# voice_board_kombi_w_gp_ordered-210217.net
KiCad netlist of a schematic drawn in EAGLE
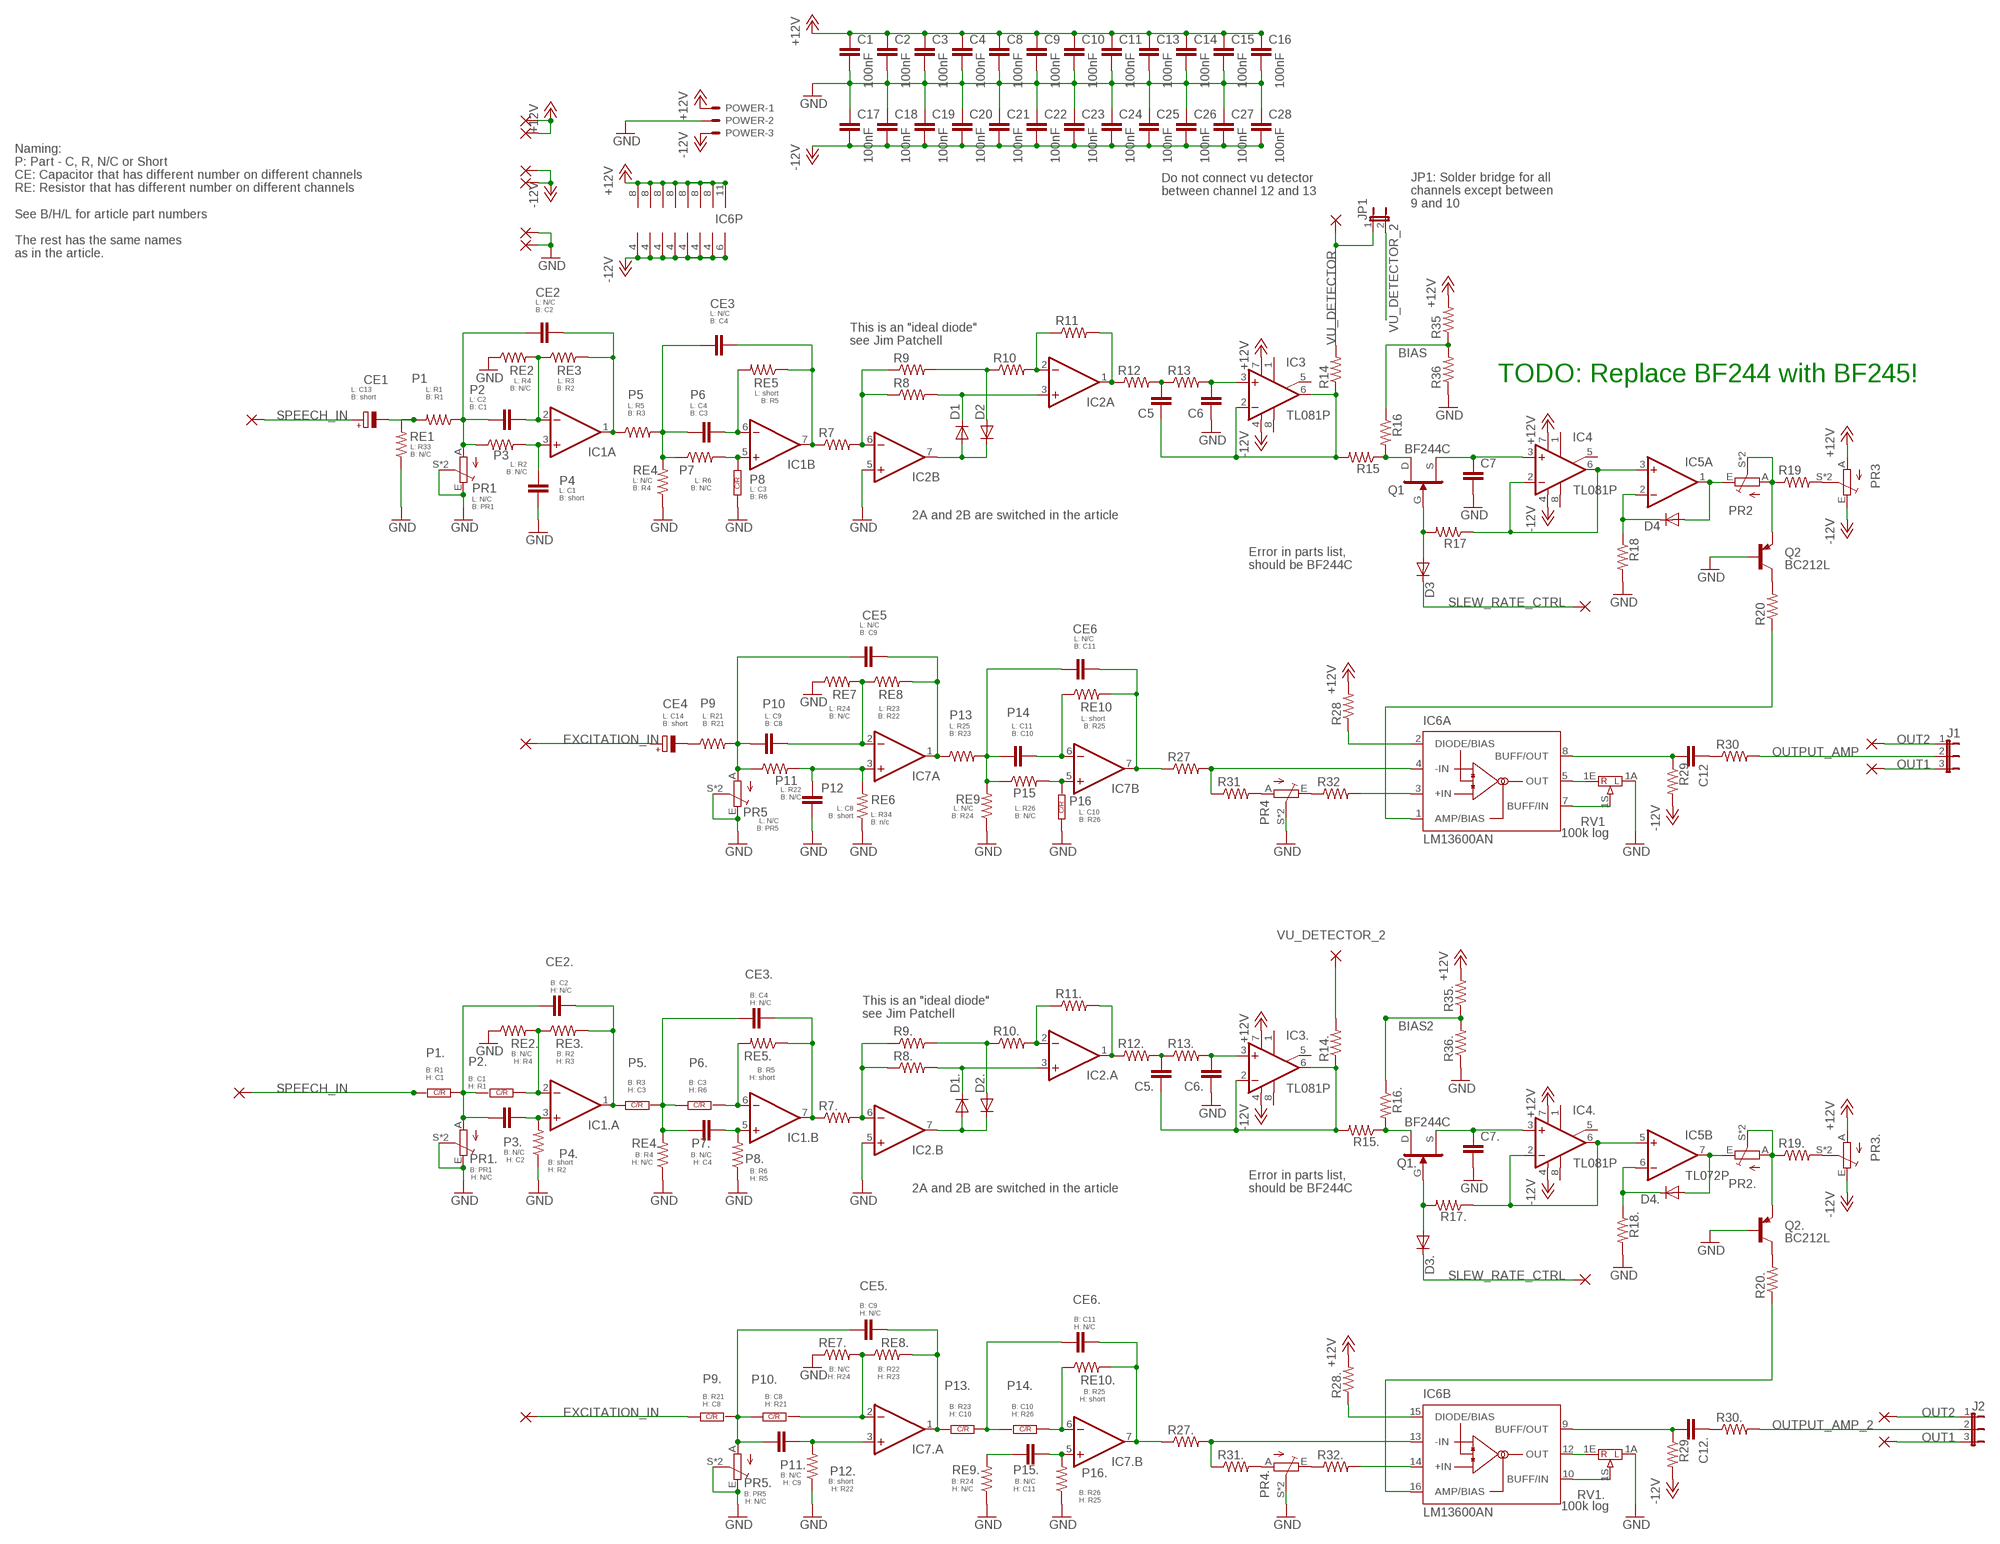
[diagram p0: schematic, sheet 1]

(export (version "E")
  (design (tool "Eeschema 10.0.6"))
  (components
    (comp (ref "C1")
      (value "100nF")
      (footprint "eagle-import:C0603")
      (libsource (lib "eagle-import") (part "C-EUC0603"))
    )
    (comp (ref "C2")
      (value "100nF")
      (footprint "eagle-import:C0603")
      (libsource (lib "eagle-import") (part "C-EUC0603"))
    )
    (comp (ref "C3")
      (value "100nF")
      (footprint "eagle-import:C0603")
      (libsource (lib "eagle-import") (part "C-EUC0603"))
    )
    (comp (ref "C4")
      (value "100nF")
      (footprint "eagle-import:C0603")
      (libsource (lib "eagle-import") (part "C-EUC0603"))
    )
    (comp (ref "C5")
      (value "C-EU050-035X075")
      (footprint "eagle-import:C050-035X075")
      (libsource (lib "eagle-import") (part "C-EU050-035X075"))
    )
    (comp (ref "C5.")
      (value "C-EU050-035X075")
      (footprint "eagle-import:C050-035X075")
      (libsource (lib "eagle-import") (part "C-EU050-035X075"))
    )
    (comp (ref "C6")
      (value "C-EU050-035X075")
      (footprint "eagle-import:C050-035X075")
      (libsource (lib "eagle-import") (part "C-EU050-035X075"))
    )
    (comp (ref "C6.")
      (value "C-EU050-035X075")
      (footprint "eagle-import:C050-035X075")
      (libsource (lib "eagle-import") (part "C-EU050-035X075"))
    )
    (comp (ref "C7")
      (value "C-EU050-035X075")
      (footprint "eagle-import:C050-035X075")
      (libsource (lib "eagle-import") (part "C-EU050-035X075"))
    )
    (comp (ref "C7.")
      (value "C-EU050-035X075")
      (footprint "eagle-import:C050-035X075")
      (libsource (lib "eagle-import") (part "C-EU050-035X075"))
    )
    (comp (ref "C8")
      (value "100nF")
      (footprint "eagle-import:C0603")
      (libsource (lib "eagle-import") (part "C-EUC0603"))
    )
    (comp (ref "C9")
      (value "100nF")
      (footprint "eagle-import:C0603")
      (libsource (lib "eagle-import") (part "C-EUC0603"))
    )
    (comp (ref "C10")
      (value "100nF")
      (footprint "eagle-import:C0603")
      (libsource (lib "eagle-import") (part "C-EUC0603"))
    )
    (comp (ref "C11")
      (value "100nF")
      (footprint "eagle-import:C0603")
      (libsource (lib "eagle-import") (part "C-EUC0603"))
    )
    (comp (ref "C12")
      (value "C-EU050-035X075")
      (footprint "eagle-import:C050-035X075")
      (libsource (lib "eagle-import") (part "C-EU050-035X075"))
    )
    (comp (ref "C12.")
      (value "C-EU050-035X075")
      (footprint "eagle-import:C050-035X075")
      (libsource (lib "eagle-import") (part "C-EU050-035X075"))
    )
    (comp (ref "C13")
      (value "100nF")
      (footprint "eagle-import:C0603")
      (libsource (lib "eagle-import") (part "C-EUC0603"))
    )
    (comp (ref "C14")
      (value "100nF")
      (footprint "eagle-import:C0603")
      (libsource (lib "eagle-import") (part "C-EUC0603"))
    )
    (comp (ref "C15")
      (value "100nF")
      (footprint "eagle-import:C0603")
      (libsource (lib "eagle-import") (part "C-EUC0603"))
    )
    (comp (ref "C16")
      (value "100nF")
      (footprint "eagle-import:C0603")
      (libsource (lib "eagle-import") (part "C-EUC0603"))
    )
    (comp (ref "C17")
      (value "100nF")
      (footprint "eagle-import:C0603")
      (libsource (lib "eagle-import") (part "C-EUC0603"))
    )
    (comp (ref "C18")
      (value "100nF")
      (footprint "eagle-import:C0603")
      (libsource (lib "eagle-import") (part "C-EUC0603"))
    )
    (comp (ref "C19")
      (value "100nF")
      (footprint "eagle-import:C0603")
      (libsource (lib "eagle-import") (part "C-EUC0603"))
    )
    (comp (ref "C20")
      (value "100nF")
      (footprint "eagle-import:C0603")
      (libsource (lib "eagle-import") (part "C-EUC0603"))
    )
    (comp (ref "C21")
      (value "100nF")
      (footprint "eagle-import:C0603")
      (libsource (lib "eagle-import") (part "C-EUC0603"))
    )
    (comp (ref "C22")
      (value "100nF")
      (footprint "eagle-import:C0603")
      (libsource (lib "eagle-import") (part "C-EUC0603"))
    )
    (comp (ref "C23")
      (value "100nF")
      (footprint "eagle-import:C0603")
      (libsource (lib "eagle-import") (part "C-EUC0603"))
    )
    (comp (ref "C24")
      (value "100nF")
      (footprint "eagle-import:C0603")
      (libsource (lib "eagle-import") (part "C-EUC0603"))
    )
    (comp (ref "C25")
      (value "100nF")
      (footprint "eagle-import:C0603")
      (libsource (lib "eagle-import") (part "C-EUC0603"))
    )
    (comp (ref "C26")
      (value "100nF")
      (footprint "eagle-import:C0603")
      (libsource (lib "eagle-import") (part "C-EUC0603"))
    )
    (comp (ref "C27")
      (value "100nF")
      (footprint "eagle-import:C0603")
      (libsource (lib "eagle-import") (part "C-EUC0603"))
    )
    (comp (ref "C28")
      (value "100nF")
      (footprint "eagle-import:C0603")
      (libsource (lib "eagle-import") (part "C-EUC0603"))
    )
    (comp (ref "CE1")
      (value "CPOL-EUE2-4")
      (footprint "eagle-import:E2-4")
      (libsource (lib "eagle-import") (part "CPOL-EUE2-4"))
    )
    (comp (ref "CE2")
      (value "C-EU050-035X075")
      (footprint "eagle-import:C050-035X075")
      (libsource (lib "eagle-import") (part "C-EU050-035X075"))
    )
    (comp (ref "CE2.")
      (value "C-EU050-035X075")
      (footprint "eagle-import:C050-035X075")
      (libsource (lib "eagle-import") (part "C-EU050-035X075"))
    )
    (comp (ref "CE3")
      (value "C-EU050-035X075")
      (footprint "eagle-import:C050-035X075")
      (libsource (lib "eagle-import") (part "C-EU050-035X075"))
    )
    (comp (ref "CE3.")
      (value "C-EU050-035X075")
      (footprint "eagle-import:C050-035X075")
      (libsource (lib "eagle-import") (part "C-EU050-035X075"))
    )
    (comp (ref "CE4")
      (value "CPOL-EUE2-4")
      (footprint "eagle-import:E2-4")
      (libsource (lib "eagle-import") (part "CPOL-EUE2-4"))
    )
    (comp (ref "CE5")
      (value "C-EU050-035X075")
      (footprint "eagle-import:C050-035X075")
      (libsource (lib "eagle-import") (part "C-EU050-035X075"))
    )
    (comp (ref "CE5.")
      (value "C-EU050-035X075")
      (footprint "eagle-import:C050-035X075")
      (libsource (lib "eagle-import") (part "C-EU050-035X075"))
    )
    (comp (ref "CE6")
      (value "C-EU050-035X075")
      (footprint "eagle-import:C050-035X075")
      (libsource (lib "eagle-import") (part "C-EU050-035X075"))
    )
    (comp (ref "CE6.")
      (value "C-EU050-035X075")
      (footprint "eagle-import:C050-035X075")
      (libsource (lib "eagle-import") (part "C-EU050-035X075"))
    )
    (comp (ref "D1")
      (value "DIODE-D-5")
      (footprint "eagle-import:D-5")
      (libsource (lib "eagle-import") (part "DIODE-D-5"))
    )
    (comp (ref "D1.")
      (value "DIODE-D-5")
      (footprint "eagle-import:D-5")
      (libsource (lib "eagle-import") (part "DIODE-D-5"))
    )
    (comp (ref "D2")
      (value "DIODE-D-5")
      (footprint "eagle-import:D-5")
      (libsource (lib "eagle-import") (part "DIODE-D-5"))
    )
    (comp (ref "D2.")
      (value "DIODE-D-5")
      (footprint "eagle-import:D-5")
      (libsource (lib "eagle-import") (part "DIODE-D-5"))
    )
    (comp (ref "D3")
      (value "DIODE-D-5")
      (footprint "eagle-import:D-5")
      (libsource (lib "eagle-import") (part "DIODE-D-5"))
    )
    (comp (ref "D3.")
      (value "DIODE-D-5")
      (footprint "eagle-import:D-5")
      (libsource (lib "eagle-import") (part "DIODE-D-5"))
    )
    (comp (ref "D4")
      (value "DIODE-D-5")
      (footprint "eagle-import:D-5")
      (libsource (lib "eagle-import") (part "DIODE-D-5"))
    )
    (comp (ref "D4.")
      (value "DIODE-D-5")
      (footprint "eagle-import:D-5")
      (libsource (lib "eagle-import") (part "DIODE-D-5"))
    )
    (comp (ref "IC1")
      (value "TL072P")
      (footprint "eagle-import:DIL08")
      (libsource (lib "eagle-import") (part "TL072P"))
    )
    (comp (ref "IC1.")
      (value "TL072P")
      (footprint "eagle-import:DIL08")
      (libsource (lib "eagle-import") (part "TL072P"))
    )
    (comp (ref "IC2")
      (value "TL072P")
      (footprint "eagle-import:DIL08")
      (libsource (lib "eagle-import") (part "TL072P"))
    )
    (comp (ref "IC2.")
      (value "TL072P")
      (footprint "eagle-import:DIL08")
      (libsource (lib "eagle-import") (part "TL072P"))
    )
    (comp (ref "IC3")
      (value "TL081P")
      (footprint "eagle-import:DIL08")
      (libsource (lib "eagle-import") (part "TL081P"))
    )
    (comp (ref "IC3.")
      (value "TL081P")
      (footprint "eagle-import:DIL08")
      (libsource (lib "eagle-import") (part "TL081P"))
    )
    (comp (ref "IC4")
      (value "TL081P")
      (footprint "eagle-import:DIL08")
      (libsource (lib "eagle-import") (part "TL081P"))
    )
    (comp (ref "IC4.")
      (value "TL081P")
      (footprint "eagle-import:DIL08")
      (libsource (lib "eagle-import") (part "TL081P"))
    )
    (comp (ref "IC5")
      (value "TL072P")
      (footprint "eagle-import:DIL08")
      (libsource (lib "eagle-import") (part "TL072P"))
    )
    (comp (ref "IC6")
      (value "LM13600AN")
      (footprint "eagle-import:DIL16")
      (libsource (lib "eagle-import") (part "LM13600NA"))
    )
    (comp (ref "IC7")
      (value "TL072P")
      (footprint "eagle-import:DIL08")
      (libsource (lib "eagle-import") (part "TL072P"))
    )
    (comp (ref "IC7.")
      (value "TL072P")
      (footprint "eagle-import:DIL08")
      (libsource (lib "eagle-import") (part "TL072P"))
    )
    (comp (ref "J1")
      (value "JP2E")
      (footprint "eagle-import:JP2")
      (libsource (lib "eagle-import") (part "JP2E"))
    )
    (comp (ref "J2")
      (value "JP2E")
      (footprint "eagle-import:JP2")
      (libsource (lib "eagle-import") (part "JP2E"))
    )
    (comp (ref "JP1")
      (value "JP1E")
      (footprint "eagle-import:JP1")
      (libsource (lib "eagle-import") (part "JP1E"))
    )
    (comp (ref "P1")
      (value "R-US_0207/7")
      (footprint "eagle-import:0207_7")
      (libsource (lib "eagle-import") (part "R-US_0207/7"))
    )
    (comp (ref "P1.")
      (value "C-OR-R050_075-035X100")
      (footprint "eagle-import:P050_075-035X100J")
      (libsource (lib "eagle-import") (part "C-OR-R050_075-035X100"))
    )
    (comp (ref "P2")
      (value "C-EU050-035X075")
      (footprint "eagle-import:C050-035X075")
      (libsource (lib "eagle-import") (part "C-EU050-035X075"))
    )
    (comp (ref "P2.")
      (value "C-OR-R050_075-035X100")
      (footprint "eagle-import:P050_075-035X100J")
      (libsource (lib "eagle-import") (part "C-OR-R050_075-035X100"))
    )
    (comp (ref "P3")
      (value "R-US_0207/7")
      (footprint "eagle-import:0207_7")
      (libsource (lib "eagle-import") (part "R-US_0207/7"))
    )
    (comp (ref "P3.")
      (value "C-EU050-035X075")
      (footprint "eagle-import:C050-035X075")
      (libsource (lib "eagle-import") (part "C-EU050-035X075"))
    )
    (comp (ref "P4")
      (value "C-EU050-035X075")
      (footprint "eagle-import:C050-035X075")
      (libsource (lib "eagle-import") (part "C-EU050-035X075"))
    )
    (comp (ref "P4.")
      (value "R-US_0207/7")
      (footprint "eagle-import:0207_7")
      (libsource (lib "eagle-import") (part "R-US_0207/7"))
    )
    (comp (ref "P5")
      (value "R-US_0207/7")
      (footprint "eagle-import:0207_7")
      (libsource (lib "eagle-import") (part "R-US_0207/7"))
    )
    (comp (ref "P5.")
      (value "C-OR-R050_075-035X100")
      (footprint "eagle-import:P050_075-035X100J")
      (libsource (lib "eagle-import") (part "C-OR-R050_075-035X100"))
    )
    (comp (ref "P6")
      (value "C-EU050-035X075")
      (footprint "eagle-import:C050-035X075")
      (libsource (lib "eagle-import") (part "C-EU050-035X075"))
    )
    (comp (ref "P6.")
      (value "C-OR-R050_075-035X100")
      (footprint "eagle-import:P050_075-035X100J")
      (libsource (lib "eagle-import") (part "C-OR-R050_075-035X100"))
    )
    (comp (ref "P7")
      (value "R-US_0207/7")
      (footprint "eagle-import:0207_7")
      (libsource (lib "eagle-import") (part "R-US_0207/7"))
    )
    (comp (ref "P7.")
      (value "C-EU050-035X075")
      (footprint "eagle-import:C050-035X075")
      (libsource (lib "eagle-import") (part "C-EU050-035X075"))
    )
    (comp (ref "P8")
      (value "C-OR-R050_075-035X100")
      (footprint "eagle-import:P050_075-035X100J")
      (libsource (lib "eagle-import") (part "C-OR-R050_075-035X100"))
    )
    (comp (ref "P8.")
      (value "R-US_0207/7")
      (footprint "eagle-import:0207_7")
      (libsource (lib "eagle-import") (part "R-US_0207/7"))
    )
    (comp (ref "P9")
      (value "R-US_0207/7")
      (footprint "eagle-import:0207_7")
      (libsource (lib "eagle-import") (part "R-US_0207/7"))
    )
    (comp (ref "P9.")
      (value "C-OR-R050_075-035X100")
      (footprint "eagle-import:P050_075-035X100J")
      (libsource (lib "eagle-import") (part "C-OR-R050_075-035X100"))
    )
    (comp (ref "P10")
      (value "C-EU050-035X075")
      (footprint "eagle-import:C050-035X075")
      (libsource (lib "eagle-import") (part "C-EU050-035X075"))
    )
    (comp (ref "P10.")
      (value "C-OR-R050_075-035X100")
      (footprint "eagle-import:P050_075-035X100J")
      (libsource (lib "eagle-import") (part "C-OR-R050_075-035X100"))
    )
    (comp (ref "P11")
      (value "R-US_0207/7")
      (footprint "eagle-import:0207_7")
      (libsource (lib "eagle-import") (part "R-US_0207/7"))
    )
    (comp (ref "P11.")
      (value "C-EU050-035X075")
      (footprint "eagle-import:C050-035X075")
      (libsource (lib "eagle-import") (part "C-EU050-035X075"))
    )
    (comp (ref "P12")
      (value "C-EU050-035X075")
      (footprint "eagle-import:C050-035X075")
      (libsource (lib "eagle-import") (part "C-EU050-035X075"))
    )
    (comp (ref "P12.")
      (value "R-US_0207/7")
      (footprint "eagle-import:0207_7")
      (libsource (lib "eagle-import") (part "R-US_0207/7"))
    )
    (comp (ref "P13")
      (value "R-US_0207/7")
      (footprint "eagle-import:0207_7")
      (libsource (lib "eagle-import") (part "R-US_0207/7"))
    )
    (comp (ref "P13.")
      (value "C-OR-R050_075-035X100")
      (footprint "eagle-import:P050_075-035X100J")
      (libsource (lib "eagle-import") (part "C-OR-R050_075-035X100"))
    )
    (comp (ref "P14")
      (value "C-EU050-035X075")
      (footprint "eagle-import:C050-035X075")
      (libsource (lib "eagle-import") (part "C-EU050-035X075"))
    )
    (comp (ref "P14.")
      (value "C-OR-R050_075-035X100")
      (footprint "eagle-import:P050_075-035X100J")
      (libsource (lib "eagle-import") (part "C-OR-R050_075-035X100"))
    )
    (comp (ref "P15")
      (value "R-US_0207/7")
      (footprint "eagle-import:0207_7")
      (libsource (lib "eagle-import") (part "R-US_0207/7"))
    )
    (comp (ref "P15.")
      (value "C-EU050-035X075")
      (footprint "eagle-import:C050-035X075")
      (libsource (lib "eagle-import") (part "C-EU050-035X075"))
    )
    (comp (ref "P16")
      (value "C-OR-R050_075-035X100")
      (footprint "eagle-import:P050_075-035X100J")
      (libsource (lib "eagle-import") (part "C-OR-R050_075-035X100"))
    )
    (comp (ref "P16.")
      (value "R-US_0207/7")
      (footprint "eagle-import:0207_7")
      (libsource (lib "eagle-import") (part "R-US_0207/7"))
    )
    (comp (ref "PAD1")
      (value "WIREPAD2,54/1,1")
      (footprint "eagle-import:2,54_1,1")
      (libsource (lib "eagle-import") (part "WIREPAD2,54/1,1"))
    )
    (comp (ref "PAD2")
      (value "WIREPAD2,54/1,1")
      (footprint "eagle-import:2,54_1,1")
      (libsource (lib "eagle-import") (part "WIREPAD2,54/1,1"))
    )
    (comp (ref "PAD3")
      (value "WIREPAD2,54/1,1")
      (footprint "eagle-import:2,54_1,1")
      (libsource (lib "eagle-import") (part "WIREPAD2,54/1,1"))
    )
    (comp (ref "PAD4")
      (value "WIREPAD2,54/1,1")
      (footprint "eagle-import:2,54_1,1")
      (libsource (lib "eagle-import") (part "WIREPAD2,54/1,1"))
    )
    (comp (ref "PAD5")
      (value "WIREPAD2,54/1,1")
      (footprint "eagle-import:2,54_1,1")
      (libsource (lib "eagle-import") (part "WIREPAD2,54/1,1"))
    )
    (comp (ref "PAD6")
      (value "WIREPAD2,54/1,1")
      (footprint "eagle-import:2,54_1,1")
      (libsource (lib "eagle-import") (part "WIREPAD2,54/1,1"))
    )
    (comp (ref "PAD7")
      (value "WIREPAD2,54/1,1")
      (footprint "eagle-import:2,54_1,1")
      (libsource (lib "eagle-import") (part "WIREPAD2,54/1,1"))
    )
    (comp (ref "PAD8")
      (value "WIREPAD2,54/1,1")
      (footprint "eagle-import:2,54_1,1")
      (libsource (lib "eagle-import") (part "WIREPAD2,54/1,1"))
    )
    (comp (ref "PAD9")
      (value "WIREPAD2,54/1,1")
      (footprint "eagle-import:2,54_1,1")
      (libsource (lib "eagle-import") (part "WIREPAD2,54/1,1"))
    )
    (comp (ref "PAD10")
      (value "WIREPAD2,54/1,1")
      (footprint "eagle-import:2,54_1,1")
      (libsource (lib "eagle-import") (part "WIREPAD2,54/1,1"))
    )
    (comp (ref "PAD11")
      (value "WIREPAD2,54/1,1")
      (footprint "eagle-import:2,54_1,1")
      (libsource (lib "eagle-import") (part "WIREPAD2,54/1,1"))
    )
    (comp (ref "PAD12")
      (value "WIREPAD2,54/1,1")
      (footprint "eagle-import:2,54_1,1")
      (libsource (lib "eagle-import") (part "WIREPAD2,54/1,1"))
    )
    (comp (ref "PAD13")
      (value "WIREPAD2,54/1,1")
      (footprint "eagle-import:2,54_1,1")
      (libsource (lib "eagle-import") (part "WIREPAD2,54/1,1"))
    )
    (comp (ref "PAD14")
      (value "WIREPAD2,54/1,1")
      (footprint "eagle-import:2,54_1,1")
      (libsource (lib "eagle-import") (part "WIREPAD2,54/1,1"))
    )
    (comp (ref "PAD15")
      (value "WIREPAD2,54/1,1")
      (footprint "eagle-import:2,54_1,1")
      (libsource (lib "eagle-import") (part "WIREPAD2,54/1,1"))
    )
    (comp (ref "PAD16")
      (value "WIREPAD2,54/1,1")
      (footprint "eagle-import:2,54_1,1")
      (libsource (lib "eagle-import") (part "WIREPAD2,54/1,1"))
    )
    (comp (ref "PAD17")
      (value "WIREPAD2,54/1,1")
      (footprint "eagle-import:2,54_1,1")
      (libsource (lib "eagle-import") (part "WIREPAD2,54/1,1"))
    )
    (comp (ref "PAD18")
      (value "WIREPAD2,54/1,1")
      (footprint "eagle-import:2,54_1,1")
      (libsource (lib "eagle-import") (part "WIREPAD2,54/1,1"))
    )
    (comp (ref "POWER")
      (value "KK-156-3")
      (footprint "eagle-import:KK-156-3")
      (libsource (lib "eagle-import") (part "KK-156-3"))
    )
    (comp (ref "PR1")
      (value "TRIM_EU-PT10-R065")
      (footprint "eagle-import:MULTIPOT_2_J")
      (libsource (lib "eagle-import") (part "TRIM_EU-PT10-R065"))
    )
    (comp (ref "PR1.")
      (value "TRIM_EU-PT10-R065")
      (footprint "eagle-import:MULTIPOT_2_J")
      (libsource (lib "eagle-import") (part "TRIM_EU-PT10-R065"))
    )
    (comp (ref "PR2")
      (value "TRIM_EU-PT10-R065")
      (footprint "eagle-import:MULTIPOT_2_J")
      (libsource (lib "eagle-import") (part "TRIM_EU-PT10-R065"))
    )
    (comp (ref "PR2.")
      (value "TRIM_EU-PT10-R065")
      (footprint "eagle-import:MULTIPOT_2_J")
      (libsource (lib "eagle-import") (part "TRIM_EU-PT10-R065"))
    )
    (comp (ref "PR3")
      (value "TRIM_EU-PT10-R065")
      (footprint "eagle-import:MULTIPOT_2_J")
      (libsource (lib "eagle-import") (part "TRIM_EU-PT10-R065"))
    )
    (comp (ref "PR3.")
      (value "TRIM_EU-PT10-R065")
      (footprint "eagle-import:MULTIPOT_2_J")
      (libsource (lib "eagle-import") (part "TRIM_EU-PT10-R065"))
    )
    (comp (ref "PR4")
      (value "TRIM_EU-PT10-R065")
      (footprint "eagle-import:MULTIPOT_2_J")
      (libsource (lib "eagle-import") (part "TRIM_EU-PT10-R065"))
    )
    (comp (ref "PR4.")
      (value "TRIM_EU-PT10-R065")
      (footprint "eagle-import:MULTIPOT_2_J")
      (libsource (lib "eagle-import") (part "TRIM_EU-PT10-R065"))
    )
    (comp (ref "PR5")
      (value "TRIM_EU-PT10-R065")
      (footprint "eagle-import:MULTIPOT_2_J")
      (libsource (lib "eagle-import") (part "TRIM_EU-PT10-R065"))
    )
    (comp (ref "PR5.")
      (value "TRIM_EU-PT10-R065")
      (footprint "eagle-import:MULTIPOT_2_J")
      (libsource (lib "eagle-import") (part "TRIM_EU-PT10-R065"))
    )
    (comp (ref "Q1")
      (value "BF244C")
      (footprint "eagle-import:TO92-DGSD-J")
      (libsource (lib "eagle-import") (part "N-CHANNEL-JFET-JIL-DGSD"))
    )
    (comp (ref "Q1.")
      (value "BF244C")
      (footprint "eagle-import:TO92-DGSD-J")
      (libsource (lib "eagle-import") (part "N-CHANNEL-JFET-JIL-DGSD"))
    )
    (comp (ref "Q2")
      (value "BC212L")
      (footprint "eagle-import:TO92-ECB")
      (libsource (lib "eagle-import") (part "-PNP-TO92-ECB"))
    )
    (comp (ref "Q2.")
      (value "BC212L")
      (footprint "eagle-import:TO92-ECB")
      (libsource (lib "eagle-import") (part "-PNP-TO92-ECB"))
    )
    (comp (ref "R7")
      (value "R-US_0207/7")
      (footprint "eagle-import:0207_7")
      (libsource (lib "eagle-import") (part "R-US_0207/7"))
    )
    (comp (ref "R7.")
      (value "R-US_0207/7")
      (footprint "eagle-import:0207_7")
      (libsource (lib "eagle-import") (part "R-US_0207/7"))
    )
    (comp (ref "R8")
      (value "R-US_0207/7")
      (footprint "eagle-import:0207_7")
      (libsource (lib "eagle-import") (part "R-US_0207/7"))
    )
    (comp (ref "R8.")
      (value "R-US_0207/7")
      (footprint "eagle-import:0207_7")
      (libsource (lib "eagle-import") (part "R-US_0207/7"))
    )
    (comp (ref "R9")
      (value "R-US_0207/7")
      (footprint "eagle-import:0207_7")
      (libsource (lib "eagle-import") (part "R-US_0207/7"))
    )
    (comp (ref "R9.")
      (value "R-US_0207/7")
      (footprint "eagle-import:0207_7")
      (libsource (lib "eagle-import") (part "R-US_0207/7"))
    )
    (comp (ref "R10")
      (value "R-US_0207/7")
      (footprint "eagle-import:0207_7")
      (libsource (lib "eagle-import") (part "R-US_0207/7"))
    )
    (comp (ref "R10.")
      (value "R-US_0207/7")
      (footprint "eagle-import:0207_7")
      (libsource (lib "eagle-import") (part "R-US_0207/7"))
    )
    (comp (ref "R11")
      (value "R-US_0207/7")
      (footprint "eagle-import:0207_7")
      (libsource (lib "eagle-import") (part "R-US_0207/7"))
    )
    (comp (ref "R11.")
      (value "R-US_0207/7")
      (footprint "eagle-import:0207_7")
      (libsource (lib "eagle-import") (part "R-US_0207/7"))
    )
    (comp (ref "R12")
      (value "R-US_0207/7")
      (footprint "eagle-import:0207_7")
      (libsource (lib "eagle-import") (part "R-US_0207/7"))
    )
    (comp (ref "R12.")
      (value "R-US_0207/7")
      (footprint "eagle-import:0207_7")
      (libsource (lib "eagle-import") (part "R-US_0207/7"))
    )
    (comp (ref "R13")
      (value "R-US_0207/7")
      (footprint "eagle-import:0207_7")
      (libsource (lib "eagle-import") (part "R-US_0207/7"))
    )
    (comp (ref "R13.")
      (value "R-US_0207/7")
      (footprint "eagle-import:0207_7")
      (libsource (lib "eagle-import") (part "R-US_0207/7"))
    )
    (comp (ref "R14")
      (value "R-US_0207/7")
      (footprint "eagle-import:0207_7")
      (libsource (lib "eagle-import") (part "R-US_0207/7"))
    )
    (comp (ref "R14.")
      (value "R-US_0207/7")
      (footprint "eagle-import:0207_7")
      (libsource (lib "eagle-import") (part "R-US_0207/7"))
    )
    (comp (ref "R15")
      (value "R-US_0207/7")
      (footprint "eagle-import:0207_7")
      (libsource (lib "eagle-import") (part "R-US_0207/7"))
    )
    (comp (ref "R15.")
      (value "R-US_0207/7")
      (footprint "eagle-import:0207_7")
      (libsource (lib "eagle-import") (part "R-US_0207/7"))
    )
    (comp (ref "R16")
      (value "R-US_0207/7")
      (footprint "eagle-import:0207_7")
      (libsource (lib "eagle-import") (part "R-US_0207/7"))
    )
    (comp (ref "R16.")
      (value "R-US_0207/7")
      (footprint "eagle-import:0207_7")
      (libsource (lib "eagle-import") (part "R-US_0207/7"))
    )
    (comp (ref "R17")
      (value "R-US_0207/7")
      (footprint "eagle-import:0207_7")
      (libsource (lib "eagle-import") (part "R-US_0207/7"))
    )
    (comp (ref "R17.")
      (value "R-US_0207/7")
      (footprint "eagle-import:0207_7")
      (libsource (lib "eagle-import") (part "R-US_0207/7"))
    )
    (comp (ref "R18")
      (value "R-US_0207/7")
      (footprint "eagle-import:0207_7")
      (libsource (lib "eagle-import") (part "R-US_0207/7"))
    )
    (comp (ref "R18.")
      (value "R-US_0207/7")
      (footprint "eagle-import:0207_7")
      (libsource (lib "eagle-import") (part "R-US_0207/7"))
    )
    (comp (ref "R19")
      (value "R-US_0207/7")
      (footprint "eagle-import:0207_7")
      (libsource (lib "eagle-import") (part "R-US_0207/7"))
    )
    (comp (ref "R19.")
      (value "R-US_0207/7")
      (footprint "eagle-import:0207_7")
      (libsource (lib "eagle-import") (part "R-US_0207/7"))
    )
    (comp (ref "R20")
      (value "R-US_0207/7")
      (footprint "eagle-import:0207_7")
      (libsource (lib "eagle-import") (part "R-US_0207/7"))
    )
    (comp (ref "R20.")
      (value "R-US_0207/7")
      (footprint "eagle-import:0207_7")
      (libsource (lib "eagle-import") (part "R-US_0207/7"))
    )
    (comp (ref "R27")
      (value "R-US_0207/7")
      (footprint "eagle-import:0207_7")
      (libsource (lib "eagle-import") (part "R-US_0207/7"))
    )
    (comp (ref "R27.")
      (value "R-US_0207/7")
      (footprint "eagle-import:0207_7")
      (libsource (lib "eagle-import") (part "R-US_0207/7"))
    )
    (comp (ref "R28")
      (value "R-US_0207/7")
      (footprint "eagle-import:0207_7")
      (libsource (lib "eagle-import") (part "R-US_0207/7"))
    )
    (comp (ref "R28.")
      (value "R-US_0207/7")
      (footprint "eagle-import:0207_7")
      (libsource (lib "eagle-import") (part "R-US_0207/7"))
    )
    (comp (ref "R29")
      (value "R-US_0207/7")
      (footprint "eagle-import:0207_7")
      (libsource (lib "eagle-import") (part "R-US_0207/7"))
    )
    (comp (ref "R29.")
      (value "R-US_0207/7")
      (footprint "eagle-import:0207_7")
      (libsource (lib "eagle-import") (part "R-US_0207/7"))
    )
    (comp (ref "R30")
      (value "R-US_0207/7")
      (footprint "eagle-import:0207_7")
      (libsource (lib "eagle-import") (part "R-US_0207/7"))
    )
    (comp (ref "R30.")
      (value "R-US_0207/7")
      (footprint "eagle-import:0207_7")
      (libsource (lib "eagle-import") (part "R-US_0207/7"))
    )
    (comp (ref "R31")
      (value "R-US_0207/7")
      (footprint "eagle-import:0207_7")
      (libsource (lib "eagle-import") (part "R-US_0207/7"))
    )
    (comp (ref "R31.")
      (value "R-US_0207/7")
      (footprint "eagle-import:0207_7")
      (libsource (lib "eagle-import") (part "R-US_0207/7"))
    )
    (comp (ref "R32")
      (value "R-US_0207/7")
      (footprint "eagle-import:0207_7")
      (libsource (lib "eagle-import") (part "R-US_0207/7"))
    )
    (comp (ref "R32.")
      (value "R-US_0207/7")
      (footprint "eagle-import:0207_7")
      (libsource (lib "eagle-import") (part "R-US_0207/7"))
    )
    (comp (ref "R35")
      (value "R-US_0207/7")
      (footprint "eagle-import:0207_7")
      (libsource (lib "eagle-import") (part "R-US_0207/7"))
    )
    (comp (ref "R35.")
      (value "R-US_0207/7")
      (footprint "eagle-import:0207_7")
      (libsource (lib "eagle-import") (part "R-US_0207/7"))
    )
    (comp (ref "R36")
      (value "R-US_0207/7")
      (footprint "eagle-import:0207_7")
      (libsource (lib "eagle-import") (part "R-US_0207/7"))
    )
    (comp (ref "R36.")
      (value "R-US_0207/7")
      (footprint "eagle-import:0207_7")
      (libsource (lib "eagle-import") (part "R-US_0207/7"))
    )
    (comp (ref "RE1")
      (value "R-US_0207/7")
      (footprint "eagle-import:0207_7")
      (libsource (lib "eagle-import") (part "R-US_0207/7"))
    )
    (comp (ref "RE2")
      (value "R-US_0207/7")
      (footprint "eagle-import:0207_7")
      (libsource (lib "eagle-import") (part "R-US_0207/7"))
    )
    (comp (ref "RE2.")
      (value "R-US_0207/7")
      (footprint "eagle-import:0207_7")
      (libsource (lib "eagle-import") (part "R-US_0207/7"))
    )
    (comp (ref "RE3")
      (value "R-US_0207/7")
      (footprint "eagle-import:0207_7")
      (libsource (lib "eagle-import") (part "R-US_0207/7"))
    )
    (comp (ref "RE3.")
      (value "R-US_0207/7")
      (footprint "eagle-import:0207_7")
      (libsource (lib "eagle-import") (part "R-US_0207/7"))
    )
    (comp (ref "RE4")
      (value "R-US_0207/7")
      (footprint "eagle-import:0207_7")
      (libsource (lib "eagle-import") (part "R-US_0207/7"))
    )
    (comp (ref "RE4.")
      (value "R-US_0207/7")
      (footprint "eagle-import:0207_7")
      (libsource (lib "eagle-import") (part "R-US_0207/7"))
    )
    (comp (ref "RE5")
      (value "R-US_0207/7")
      (footprint "eagle-import:0207_7")
      (libsource (lib "eagle-import") (part "R-US_0207/7"))
    )
    (comp (ref "RE5.")
      (value "R-US_0207/7")
      (footprint "eagle-import:0207_7")
      (libsource (lib "eagle-import") (part "R-US_0207/7"))
    )
    (comp (ref "RE6")
      (value "R-US_0204/7")
      (footprint "eagle-import:0204_7")
      (libsource (lib "eagle-import") (part "R-US_0204/7"))
    )
    (comp (ref "RE7")
      (value "R-US_0207/7")
      (footprint "eagle-import:0207_7")
      (libsource (lib "eagle-import") (part "R-US_0207/7"))
    )
    (comp (ref "RE7.")
      (value "R-US_0207/7")
      (footprint "eagle-import:0207_7")
      (libsource (lib "eagle-import") (part "R-US_0207/7"))
    )
    (comp (ref "RE8")
      (value "R-US_0207/7")
      (footprint "eagle-import:0207_7")
      (libsource (lib "eagle-import") (part "R-US_0207/7"))
    )
    (comp (ref "RE8.")
      (value "R-US_0207/7")
      (footprint "eagle-import:0207_7")
      (libsource (lib "eagle-import") (part "R-US_0207/7"))
    )
    (comp (ref "RE9")
      (value "R-US_0207/7")
      (footprint "eagle-import:0207_7")
      (libsource (lib "eagle-import") (part "R-US_0207/7"))
    )
    (comp (ref "RE9.")
      (value "R-US_0207/7")
      (footprint "eagle-import:0207_7")
      (libsource (lib "eagle-import") (part "R-US_0207/7"))
    )
    (comp (ref "RE10")
      (value "R-US_0207/7")
      (footprint "eagle-import:0207_7")
      (libsource (lib "eagle-import") (part "R-US_0207/7"))
    )
    (comp (ref "RE10.")
      (value "R-US_0207/7")
      (footprint "eagle-import:0207_7")
      (libsource (lib "eagle-import") (part "R-US_0207/7"))
    )
    (comp (ref "RV1")
      (value "100k log")
      (footprint "eagle-import:POT16_W_BRACKET-J")
      (libsource (lib "eagle-import") (part "POT16_W_BRACKET{dblquote}{dblquote}"))
    )
    (comp (ref "RV1.")
      (value "100k log")
      (footprint "eagle-import:POT16_W_BRACKET-J")
      (libsource (lib "eagle-import") (part "POT16_W_BRACKET{dblquote}{dblquote}"))
    )
  )
  (nets
    (net (code "1") (name "+12V") (class "Default")
      (node (ref "C1") (pin "1") (pinfunction "1_1") (pintype "passive"))
      (node (ref "C10") (pin "1") (pinfunction "1_1") (pintype "passive"))
      (node (ref "C11") (pin "1") (pinfunction "1_1") (pintype "passive"))
      (node (ref "C13") (pin "1") (pinfunction "1_1") (pintype "passive"))
      (node (ref "C14") (pin "1") (pinfunction "1_1") (pintype "passive"))
      (node (ref "C15") (pin "1") (pinfunction "1_1") (pintype "passive"))
      (node (ref "C16") (pin "1") (pinfunction "1_1") (pintype "passive"))
      (node (ref "C2") (pin "1") (pinfunction "1_1") (pintype "passive"))
      (node (ref "C3") (pin "1") (pinfunction "1_1") (pintype "passive"))
      (node (ref "C4") (pin "1") (pinfunction "1_1") (pintype "passive"))
      (node (ref "C8") (pin "1") (pinfunction "1_1") (pintype "passive"))
      (node (ref "C9") (pin "1") (pinfunction "1_1") (pintype "passive"))
      (node (ref "IC1") (pin "8") (pinfunction "V+_8") (pintype "power_in"))
      (node (ref "IC1.") (pin "8") (pinfunction "V+_8") (pintype "power_in"))
      (node (ref "IC2") (pin "8") (pinfunction "V+_8") (pintype "power_in"))
      (node (ref "IC2.") (pin "8") (pinfunction "V+_8") (pintype "power_in"))
      (node (ref "IC3") (pin "7") (pinfunction "V+_7") (pintype "power_in"))
      (node (ref "IC3.") (pin "7") (pinfunction "V+_7") (pintype "power_in"))
      (node (ref "IC4") (pin "7") (pinfunction "V+_7") (pintype "power_in"))
      (node (ref "IC4.") (pin "7") (pinfunction "V+_7") (pintype "power_in"))
      (node (ref "IC5") (pin "8") (pinfunction "V+_8") (pintype "power_in"))
      (node (ref "IC6") (pin "11") (pinfunction "V+_11") (pintype "power_in"))
      (node (ref "IC7") (pin "8") (pinfunction "V+_8") (pintype "power_in"))
      (node (ref "IC7.") (pin "8") (pinfunction "V+_8") (pintype "power_in"))
      (node (ref "PAD10") (pin "1") (pinfunction "P_1") (pintype "passive"))
      (node (ref "PAD9") (pin "1") (pinfunction "P_1") (pintype "passive"))
      (node (ref "POWER") (pin "1") (pinfunction "S_1") (pintype "passive"))
      (node (ref "PR3") (pin "A") (pinfunction "A_A") (pintype "passive"))
      (node (ref "PR3.") (pin "A") (pinfunction "A_A") (pintype "passive"))
      (node (ref "R28") (pin "2") (pinfunction "2_2") (pintype "passive"))
      (node (ref "R28.") (pin "2") (pinfunction "2_2") (pintype "passive"))
      (node (ref "R35") (pin "2") (pinfunction "2_2") (pintype "passive"))
      (node (ref "R35.") (pin "2") (pinfunction "2_2") (pintype "passive"))
    )
    (net (code "2") (name "-12V") (class "Default")
      (node (ref "C17") (pin "2") (pinfunction "2_2") (pintype "passive"))
      (node (ref "C18") (pin "2") (pinfunction "2_2") (pintype "passive"))
      (node (ref "C19") (pin "2") (pinfunction "2_2") (pintype "passive"))
      (node (ref "C20") (pin "2") (pinfunction "2_2") (pintype "passive"))
      (node (ref "C21") (pin "2") (pinfunction "2_2") (pintype "passive"))
      (node (ref "C22") (pin "2") (pinfunction "2_2") (pintype "passive"))
      (node (ref "C23") (pin "2") (pinfunction "2_2") (pintype "passive"))
      (node (ref "C24") (pin "2") (pinfunction "2_2") (pintype "passive"))
      (node (ref "C25") (pin "2") (pinfunction "2_2") (pintype "passive"))
      (node (ref "C26") (pin "2") (pinfunction "2_2") (pintype "passive"))
      (node (ref "C27") (pin "2") (pinfunction "2_2") (pintype "passive"))
      (node (ref "C28") (pin "2") (pinfunction "2_2") (pintype "passive"))
      (node (ref "IC1") (pin "4") (pinfunction "V-_4") (pintype "power_in"))
      (node (ref "IC1.") (pin "4") (pinfunction "V-_4") (pintype "power_in"))
      (node (ref "IC2") (pin "4") (pinfunction "V-_4") (pintype "power_in"))
      (node (ref "IC2.") (pin "4") (pinfunction "V-_4") (pintype "power_in"))
      (node (ref "IC3") (pin "4") (pinfunction "V-_4") (pintype "power_in"))
      (node (ref "IC3.") (pin "4") (pinfunction "V-_4") (pintype "power_in"))
      (node (ref "IC4") (pin "4") (pinfunction "V-_4") (pintype "power_in"))
      (node (ref "IC4.") (pin "4") (pinfunction "V-_4") (pintype "power_in"))
      (node (ref "IC5") (pin "4") (pinfunction "V-_4") (pintype "power_in"))
      (node (ref "IC6") (pin "6") (pinfunction "V-_6") (pintype "power_in"))
      (node (ref "IC7") (pin "4") (pinfunction "V-_4") (pintype "power_in"))
      (node (ref "IC7.") (pin "4") (pinfunction "V-_4") (pintype "power_in"))
      (node (ref "PAD13") (pin "1") (pinfunction "P_1") (pintype "passive"))
      (node (ref "PAD14") (pin "1") (pinfunction "P_1") (pintype "passive"))
      (node (ref "POWER") (pin "3") (pinfunction "S_3") (pintype "passive"))
      (node (ref "PR3") (pin "E") (pinfunction "E_E") (pintype "passive"))
      (node (ref "PR3.") (pin "E") (pinfunction "E_E") (pintype "passive"))
      (node (ref "R29") (pin "2") (pinfunction "2_2") (pintype "passive"))
      (node (ref "R29.") (pin "2") (pinfunction "2_2") (pintype "passive"))
    )
    (net (code "3") (name "/BIAS") (class "Default")
      (node (ref "R16") (pin "1") (pinfunction "1_1") (pintype "passive"))
      (node (ref "R35") (pin "1") (pinfunction "1_1") (pintype "passive"))
      (node (ref "R36") (pin "2") (pinfunction "2_2") (pintype "passive"))
    )
    (net (code "4") (name "/BIAS2") (class "Default")
      (node (ref "R16.") (pin "1") (pinfunction "1_1") (pintype "passive"))
      (node (ref "R35.") (pin "1") (pinfunction "1_1") (pintype "passive"))
      (node (ref "R36.") (pin "2") (pinfunction "2_2") (pintype "passive"))
    )
    (net (code "5") (name "/EXCITATION_IN") (class "Default")
      (node (ref "CE4") (pin "+") (pinfunction "+_+") (pintype "passive"))
      (node (ref "P9.") (pin "1") (pinfunction "1_1") (pintype "passive"))
      (node (ref "PAD3") (pin "1") (pinfunction "P_1") (pintype "passive"))
      (node (ref "PAD4") (pin "1") (pinfunction "P_1") (pintype "passive"))
    )
    (net (code "6") (name "/OUT1") (class "Default")
      (node (ref "J1") (pin "3") (pinfunction "3_3") (pintype "passive"))
      (node (ref "J2") (pin "3") (pinfunction "3_3") (pintype "passive"))
      (node (ref "PAD1") (pin "1") (pinfunction "P_1") (pintype "passive"))
      (node (ref "PAD2") (pin "1") (pinfunction "P_1") (pintype "passive"))
    )
    (net (code "7") (name "/OUT2") (class "Default")
      (node (ref "J1") (pin "1") (pinfunction "1_1") (pintype "passive"))
      (node (ref "J2") (pin "1") (pinfunction "1_1") (pintype "passive"))
      (node (ref "PAD17") (pin "1") (pinfunction "P_1") (pintype "passive"))
      (node (ref "PAD18") (pin "1") (pinfunction "P_1") (pintype "passive"))
    )
    (net (code "8") (name "/OUTPUT_AMP") (class "Default")
      (node (ref "J1") (pin "2") (pinfunction "2_2") (pintype "passive"))
      (node (ref "R30") (pin "2") (pinfunction "2_2") (pintype "passive"))
    )
    (net (code "9") (name "/OUTPUT_AMP_2") (class "Default")
      (node (ref "J2") (pin "2") (pinfunction "2_2") (pintype "passive"))
      (node (ref "R30.") (pin "2") (pinfunction "2_2") (pintype "passive"))
    )
    (net (code "10") (name "/SLEW_RATE_CTRL") (class "Default")
      (node (ref "D3") (pin "C") (pinfunction "C_C") (pintype "passive"))
      (node (ref "D3.") (pin "C") (pinfunction "C_C") (pintype "passive"))
      (node (ref "PAD11") (pin "1") (pinfunction "P_1") (pintype "passive"))
      (node (ref "PAD12") (pin "1") (pinfunction "P_1") (pintype "passive"))
    )
    (net (code "11") (name "/SPEECH_IN") (class "Default")
      (node (ref "CE1") (pin "+") (pinfunction "+_+") (pintype "passive"))
      (node (ref "P1.") (pin "2") (pinfunction "2_2") (pintype "passive"))
      (node (ref "P1.") (pin "3") (pinfunction "2_3") (pintype "passive"))
      (node (ref "PAD5") (pin "1") (pinfunction "P_1") (pintype "passive"))
      (node (ref "PAD6") (pin "1") (pinfunction "P_1") (pintype "passive"))
    )
    (net (code "12") (name "/VU_DETECTOR") (class "Default")
      (node (ref "JP1") (pin "1") (pinfunction "1_1") (pintype "passive"))
      (node (ref "PAD7") (pin "1") (pinfunction "P_1") (pintype "passive"))
      (node (ref "R14") (pin "2") (pinfunction "2_2") (pintype "passive"))
    )
    (net (code "13") (name "/VU_DETECTOR_2") (class "Default")
      (node (ref "JP1") (pin "2") (pinfunction "2_2") (pintype "passive"))
      (node (ref "PAD8") (pin "1") (pinfunction "P_1") (pintype "passive"))
      (node (ref "R14.") (pin "2") (pinfunction "2_2") (pintype "passive"))
    )
    (net (code "14") (name "GND") (class "Default")
      (node (ref "C1") (pin "2") (pinfunction "2_2") (pintype "passive"))
      (node (ref "C10") (pin "2") (pinfunction "2_2") (pintype "passive"))
      (node (ref "C11") (pin "2") (pinfunction "2_2") (pintype "passive"))
      (node (ref "C13") (pin "2") (pinfunction "2_2") (pintype "passive"))
      (node (ref "C14") (pin "2") (pinfunction "2_2") (pintype "passive"))
      (node (ref "C15") (pin "2") (pinfunction "2_2") (pintype "passive"))
      (node (ref "C16") (pin "2") (pinfunction "2_2") (pintype "passive"))
      (node (ref "C17") (pin "1") (pinfunction "1_1") (pintype "passive"))
      (node (ref "C18") (pin "1") (pinfunction "1_1") (pintype "passive"))
      (node (ref "C19") (pin "1") (pinfunction "1_1") (pintype "passive"))
      (node (ref "C2") (pin "2") (pinfunction "2_2") (pintype "passive"))
      (node (ref "C20") (pin "1") (pinfunction "1_1") (pintype "passive"))
      (node (ref "C21") (pin "1") (pinfunction "1_1") (pintype "passive"))
      (node (ref "C22") (pin "1") (pinfunction "1_1") (pintype "passive"))
      (node (ref "C23") (pin "1") (pinfunction "1_1") (pintype "passive"))
      (node (ref "C24") (pin "1") (pinfunction "1_1") (pintype "passive"))
      (node (ref "C25") (pin "1") (pinfunction "1_1") (pintype "passive"))
      (node (ref "C26") (pin "1") (pinfunction "1_1") (pintype "passive"))
      (node (ref "C27") (pin "1") (pinfunction "1_1") (pintype "passive"))
      (node (ref "C28") (pin "1") (pinfunction "1_1") (pintype "passive"))
      (node (ref "C3") (pin "2") (pinfunction "2_2") (pintype "passive"))
      (node (ref "C4") (pin "2") (pinfunction "2_2") (pintype "passive"))
      (node (ref "C6") (pin "1") (pinfunction "1_1") (pintype "passive"))
      (node (ref "C6.") (pin "1") (pinfunction "1_1") (pintype "passive"))
      (node (ref "C7") (pin "2") (pinfunction "2_2") (pintype "passive"))
      (node (ref "C7.") (pin "2") (pinfunction "2_2") (pintype "passive"))
      (node (ref "C8") (pin "2") (pinfunction "2_2") (pintype "passive"))
      (node (ref "C9") (pin "2") (pinfunction "2_2") (pintype "passive"))
      (node (ref "IC2") (pin "5") (pinfunction "+IN_5") (pintype "input"))
      (node (ref "IC2.") (pin "5") (pinfunction "+IN_5") (pintype "input"))
      (node (ref "P12") (pin "1") (pinfunction "1_1") (pintype "passive"))
      (node (ref "P12.") (pin "1") (pinfunction "1_1") (pintype "passive"))
      (node (ref "P16") (pin "1") (pinfunction "1_1") (pintype "passive"))
      (node (ref "P16.") (pin "1") (pinfunction "1_1") (pintype "passive"))
      (node (ref "P4") (pin "1") (pinfunction "1_1") (pintype "passive"))
      (node (ref "P4.") (pin "1") (pinfunction "1_1") (pintype "passive"))
      (node (ref "P8") (pin "1") (pinfunction "1_1") (pintype "passive"))
      (node (ref "P8.") (pin "1") (pinfunction "1_1") (pintype "passive"))
      (node (ref "PAD15") (pin "1") (pinfunction "P_1") (pintype "passive"))
      (node (ref "PAD16") (pin "1") (pinfunction "P_1") (pintype "passive"))
      (node (ref "POWER") (pin "2") (pinfunction "S_2") (pintype "passive"))
      (node (ref "PR1") (pin "E") (pinfunction "E_E") (pintype "passive"))
      (node (ref "PR1") (pin "S") (pinfunction "S_S") (pintype "passive"))
      (node (ref "PR1") (pin "S0") (pinfunction "S_S0") (pintype "passive"))
      (node (ref "PR1.") (pin "E") (pinfunction "E_E") (pintype "passive"))
      (node (ref "PR1.") (pin "S") (pinfunction "S_S") (pintype "passive"))
      (node (ref "PR1.") (pin "S0") (pinfunction "S_S0") (pintype "passive"))
      (node (ref "PR4") (pin "S") (pinfunction "S_S") (pintype "passive"))
      (node (ref "PR4") (pin "S0") (pinfunction "S_S0") (pintype "passive"))
      (node (ref "PR4.") (pin "S") (pinfunction "S_S") (pintype "passive"))
      (node (ref "PR4.") (pin "S0") (pinfunction "S_S0") (pintype "passive"))
      (node (ref "PR5") (pin "E") (pinfunction "E_E") (pintype "passive"))
      (node (ref "PR5") (pin "S") (pinfunction "S_S") (pintype "passive"))
      (node (ref "PR5") (pin "S0") (pinfunction "S_S0") (pintype "passive"))
      (node (ref "PR5.") (pin "E") (pinfunction "E_E") (pintype "passive"))
      (node (ref "PR5.") (pin "S") (pinfunction "S_S") (pintype "passive"))
      (node (ref "PR5.") (pin "S0") (pinfunction "S_S0") (pintype "passive"))
      (node (ref "Q2") (pin "B") (pinfunction "B_B") (pintype "passive"))
      (node (ref "Q2.") (pin "B") (pinfunction "B_B") (pintype "passive"))
      (node (ref "R18") (pin "2") (pinfunction "2_2") (pintype "passive"))
      (node (ref "R18.") (pin "2") (pinfunction "2_2") (pintype "passive"))
      (node (ref "R36") (pin "1") (pinfunction "1_1") (pintype "passive"))
      (node (ref "R36.") (pin "1") (pinfunction "1_1") (pintype "passive"))
      (node (ref "RE1") (pin "1") (pinfunction "1_1") (pintype "passive"))
      (node (ref "RE2") (pin "1") (pinfunction "1_1") (pintype "passive"))
      (node (ref "RE2.") (pin "1") (pinfunction "1_1") (pintype "passive"))
      (node (ref "RE4") (pin "1") (pinfunction "1_1") (pintype "passive"))
      (node (ref "RE4.") (pin "1") (pinfunction "1_1") (pintype "passive"))
      (node (ref "RE6") (pin "1") (pinfunction "1_1") (pintype "passive"))
      (node (ref "RE7") (pin "1") (pinfunction "1_1") (pintype "passive"))
      (node (ref "RE7.") (pin "1") (pinfunction "1_1") (pintype "passive"))
      (node (ref "RE9") (pin "1") (pinfunction "1_1") (pintype "passive"))
      (node (ref "RE9.") (pin "1") (pinfunction "1_1") (pintype "passive"))
      (node (ref "RV1") (pin "1A") (pinfunction "1A_1A") (pintype "passive"))
      (node (ref "RV1.") (pin "1A") (pinfunction "1A_1A") (pintype "passive"))
    )
    (net (code "15") (name "Net-(C5-Pad2)") (class "Default")
      (node (ref "C5") (pin "2") (pinfunction "2_2") (pintype "passive"))
      (node (ref "R12") (pin "2") (pinfunction "2_2") (pintype "passive"))
      (node (ref "R13") (pin "1") (pinfunction "1_1") (pintype "passive"))
    )
    (net (code "16") (name "Net-(C5.-Pad2)") (class "Default")
      (node (ref "C5.") (pin "2") (pinfunction "2_2") (pintype "passive"))
      (node (ref "R12.") (pin "2") (pinfunction "2_2") (pintype "passive"))
      (node (ref "R13.") (pin "1") (pinfunction "1_1") (pintype "passive"))
    )
    (net (code "17") (name "Net-(C12-Pad1)") (class "Default")
      (node (ref "C12") (pin "1") (pinfunction "1_1") (pintype "passive"))
      (node (ref "R30") (pin "1") (pinfunction "1_1") (pintype "passive"))
    )
    (net (code "18") (name "Net-(C12.-Pad1)") (class "Default")
      (node (ref "C12.") (pin "1") (pinfunction "1_1") (pintype "passive"))
      (node (ref "R30.") (pin "1") (pinfunction "1_1") (pintype "passive"))
    )
    (net (code "19") (name "Net-(CE1-Pad-)") (class "Default")
      (node (ref "CE1") (pin "-") (pinfunction "-_-") (pintype "passive"))
      (node (ref "P1") (pin "2") (pinfunction "2_2") (pintype "passive"))
      (node (ref "RE1") (pin "2") (pinfunction "2_2") (pintype "passive"))
    )
    (net (code "20") (name "Net-(CE2-Pad1)") (class "Default")
      (node (ref "CE2") (pin "1") (pinfunction "1_1") (pintype "passive"))
      (node (ref "P1") (pin "1") (pinfunction "1_1") (pintype "passive"))
      (node (ref "P2") (pin "1") (pinfunction "1_1") (pintype "passive"))
      (node (ref "P3") (pin "1") (pinfunction "1_1") (pintype "passive"))
      (node (ref "PR1") (pin "A") (pinfunction "A_A") (pintype "passive"))
    )
    (net (code "21") (name "Net-(CE2.-Pad1)") (class "Default")
      (node (ref "CE2.") (pin "1") (pinfunction "1_1") (pintype "passive"))
      (node (ref "P1.") (pin "1") (pinfunction "1_1") (pintype "passive"))
      (node (ref "P2.") (pin "2") (pinfunction "2_2") (pintype "passive"))
      (node (ref "P2.") (pin "3") (pinfunction "2_3") (pintype "passive"))
      (node (ref "P3.") (pin "1") (pinfunction "1_1") (pintype "passive"))
      (node (ref "PR1.") (pin "A") (pinfunction "A_A") (pintype "passive"))
    )
    (net (code "22") (name "Net-(CE3-Pad1)") (class "Default")
      (node (ref "CE3") (pin "1") (pinfunction "1_1") (pintype "passive"))
      (node (ref "P5") (pin "2") (pinfunction "2_2") (pintype "passive"))
      (node (ref "P6") (pin "1") (pinfunction "1_1") (pintype "passive"))
      (node (ref "P7") (pin "1") (pinfunction "1_1") (pintype "passive"))
      (node (ref "RE4") (pin "2") (pinfunction "2_2") (pintype "passive"))
    )
    (net (code "23") (name "Net-(CE3.-Pad1)") (class "Default")
      (node (ref "CE3.") (pin "1") (pinfunction "1_1") (pintype "passive"))
      (node (ref "P5.") (pin "2") (pinfunction "2_2") (pintype "passive"))
      (node (ref "P5.") (pin "3") (pinfunction "2_3") (pintype "passive"))
      (node (ref "P6.") (pin "1") (pinfunction "1_1") (pintype "passive"))
      (node (ref "P7.") (pin "1") (pinfunction "1_1") (pintype "passive"))
      (node (ref "RE4.") (pin "2") (pinfunction "2_2") (pintype "passive"))
    )
    (net (code "24") (name "Net-(CE4-Pad-)") (class "Default")
      (node (ref "CE4") (pin "-") (pinfunction "-_-") (pintype "passive"))
      (node (ref "P9") (pin "1") (pinfunction "1_1") (pintype "passive"))
    )
    (net (code "25") (name "Net-(CE5-Pad2)") (class "Default")
      (node (ref "CE5") (pin "2") (pinfunction "2_2") (pintype "passive"))
      (node (ref "P10") (pin "2") (pinfunction "2_2") (pintype "passive"))
      (node (ref "P11") (pin "1") (pinfunction "1_1") (pintype "passive"))
      (node (ref "P9") (pin "2") (pinfunction "2_2") (pintype "passive"))
      (node (ref "PR5") (pin "A") (pinfunction "A_A") (pintype "passive"))
    )
    (net (code "26") (name "Net-(CE5.-Pad2)") (class "Default")
      (node (ref "CE5.") (pin "2") (pinfunction "2_2") (pintype "passive"))
      (node (ref "P10.") (pin "1") (pinfunction "1_1") (pintype "passive"))
      (node (ref "P11.") (pin "1") (pinfunction "1_1") (pintype "passive"))
      (node (ref "P9.") (pin "2") (pinfunction "2_2") (pintype "passive"))
      (node (ref "P9.") (pin "3") (pinfunction "2_3") (pintype "passive"))
      (node (ref "PR5.") (pin "A") (pinfunction "A_A") (pintype "passive"))
    )
    (net (code "27") (name "Net-(CE6-Pad2)") (class "Default")
      (node (ref "CE6") (pin "2") (pinfunction "2_2") (pintype "passive"))
      (node (ref "P13") (pin "2") (pinfunction "2_2") (pintype "passive"))
      (node (ref "P14") (pin "2") (pinfunction "2_2") (pintype "passive"))
      (node (ref "P15") (pin "1") (pinfunction "1_1") (pintype "passive"))
      (node (ref "RE9") (pin "2") (pinfunction "2_2") (pintype "passive"))
    )
    (net (code "28") (name "Net-(CE6.-Pad2)") (class "Default")
      (node (ref "CE6.") (pin "2") (pinfunction "2_2") (pintype "passive"))
      (node (ref "P13.") (pin "1") (pinfunction "1_1") (pintype "passive"))
      (node (ref "P14.") (pin "2") (pinfunction "2_2") (pintype "passive"))
      (node (ref "P14.") (pin "3") (pinfunction "2_3") (pintype "passive"))
    )
    (net (code "29") (name "Net-(D2-PadA)") (class "Default")
      (node (ref "D2") (pin "A") (pinfunction "A_A") (pintype "passive"))
      (node (ref "R10") (pin "1") (pinfunction "1_1") (pintype "passive"))
      (node (ref "R9") (pin "2") (pinfunction "2_2") (pintype "passive"))
    )
    (net (code "30") (name "Net-(D2.-PadA)") (class "Default")
      (node (ref "D2.") (pin "A") (pinfunction "A_A") (pintype "passive"))
      (node (ref "R10.") (pin "1") (pinfunction "1_1") (pintype "passive"))
      (node (ref "R9.") (pin "2") (pinfunction "2_2") (pintype "passive"))
    )
    (net (code "31") (name "Net-(D3-PadA)") (class "Default")
      (node (ref "D3") (pin "A") (pinfunction "A_A") (pintype "passive"))
      (node (ref "Q1") (pin "G") (pinfunction "G_G") (pintype "passive"))
      (node (ref "R17") (pin "2") (pinfunction "2_2") (pintype "passive"))
    )
    (net (code "32") (name "Net-(D3.-PadA)") (class "Default")
      (node (ref "D3.") (pin "A") (pinfunction "A_A") (pintype "passive"))
      (node (ref "Q1.") (pin "G") (pinfunction "G_G") (pintype "passive"))
      (node (ref "R17.") (pin "2") (pinfunction "2_2") (pintype "passive"))
    )
    (net (code "33") (name "Net-(IC1.A-+IN)") (class "Default")
      (node (ref "IC1.") (pin "3") (pinfunction "+IN_3") (pintype "input"))
      (node (ref "P3.") (pin "2") (pinfunction "2_2") (pintype "passive"))
      (node (ref "P4.") (pin "2") (pinfunction "2_2") (pintype "passive"))
    )
    (net (code "34") (name "Net-(IC1.A--IN)") (class "Default")
      (node (ref "IC1.") (pin "2") (pinfunction "-IN_2") (pintype "input"))
      (node (ref "P2.") (pin "1") (pinfunction "1_1") (pintype "passive"))
      (node (ref "RE2.") (pin "2") (pinfunction "2_2") (pintype "passive"))
      (node (ref "RE3.") (pin "1") (pinfunction "1_1") (pintype "passive"))
    )
    (net (code "35") (name "Net-(IC1.A-OUT)") (class "Default")
      (node (ref "CE2.") (pin "2") (pinfunction "2_2") (pintype "passive"))
      (node (ref "IC1.") (pin "1") (pinfunction "OUT_1") (pintype "output"))
      (node (ref "P5.") (pin "1") (pinfunction "1_1") (pintype "passive"))
      (node (ref "RE3.") (pin "2") (pinfunction "2_2") (pintype "passive"))
    )
    (net (code "36") (name "Net-(IC1.B-+IN)") (class "Default")
      (node (ref "IC1.") (pin "5") (pinfunction "+IN_5") (pintype "input"))
      (node (ref "P7.") (pin "2") (pinfunction "2_2") (pintype "passive"))
      (node (ref "P8.") (pin "2") (pinfunction "2_2") (pintype "passive"))
    )
    (net (code "37") (name "Net-(IC1.B--IN)") (class "Default")
      (node (ref "IC1.") (pin "6") (pinfunction "-IN_6") (pintype "input"))
      (node (ref "P6.") (pin "2") (pinfunction "2_2") (pintype "passive"))
      (node (ref "P6.") (pin "3") (pinfunction "2_3") (pintype "passive"))
      (node (ref "RE5.") (pin "2") (pinfunction "2_2") (pintype "passive"))
    )
    (net (code "38") (name "Net-(IC1.B-OUT)") (class "Default")
      (node (ref "CE3.") (pin "2") (pinfunction "2_2") (pintype "passive"))
      (node (ref "IC1.") (pin "7") (pinfunction "OUT_7") (pintype "output"))
      (node (ref "R7.") (pin "1") (pinfunction "1_1") (pintype "passive"))
      (node (ref "RE5.") (pin "1") (pinfunction "1_1") (pintype "passive"))
    )
    (net (code "39") (name "Net-(IC1A-+IN)") (class "Default")
      (node (ref "IC1") (pin "3") (pinfunction "+IN_3") (pintype "input"))
      (node (ref "P3") (pin "2") (pinfunction "2_2") (pintype "passive"))
      (node (ref "P4") (pin "2") (pinfunction "2_2") (pintype "passive"))
    )
    (net (code "40") (name "Net-(IC1A--IN)") (class "Default")
      (node (ref "IC1") (pin "2") (pinfunction "-IN_2") (pintype "input"))
      (node (ref "P2") (pin "2") (pinfunction "2_2") (pintype "passive"))
      (node (ref "RE2") (pin "2") (pinfunction "2_2") (pintype "passive"))
      (node (ref "RE3") (pin "1") (pinfunction "1_1") (pintype "passive"))
    )
    (net (code "41") (name "Net-(IC1A-OUT)") (class "Default")
      (node (ref "CE2") (pin "2") (pinfunction "2_2") (pintype "passive"))
      (node (ref "IC1") (pin "1") (pinfunction "OUT_1") (pintype "output"))
      (node (ref "P5") (pin "1") (pinfunction "1_1") (pintype "passive"))
      (node (ref "RE3") (pin "2") (pinfunction "2_2") (pintype "passive"))
    )
    (net (code "42") (name "Net-(IC1B-+IN)") (class "Default")
      (node (ref "IC1") (pin "5") (pinfunction "+IN_5") (pintype "input"))
      (node (ref "P7") (pin "2") (pinfunction "2_2") (pintype "passive"))
      (node (ref "P8") (pin "2") (pinfunction "2_2") (pintype "passive"))
      (node (ref "P8") (pin "3") (pinfunction "2_3") (pintype "passive"))
    )
    (net (code "43") (name "Net-(IC1B--IN)") (class "Default")
      (node (ref "IC1") (pin "6") (pinfunction "-IN_6") (pintype "input"))
      (node (ref "P6") (pin "2") (pinfunction "2_2") (pintype "passive"))
      (node (ref "RE5") (pin "2") (pinfunction "2_2") (pintype "passive"))
    )
    (net (code "44") (name "Net-(IC1B-OUT)") (class "Default")
      (node (ref "CE3") (pin "2") (pinfunction "2_2") (pintype "passive"))
      (node (ref "IC1") (pin "7") (pinfunction "OUT_7") (pintype "output"))
      (node (ref "R7") (pin "1") (pinfunction "1_1") (pintype "passive"))
      (node (ref "RE5") (pin "1") (pinfunction "1_1") (pintype "passive"))
    )
    (net (code "45") (name "Net-(IC2.A-+IN)") (class "Default")
      (node (ref "D1.") (pin "C") (pinfunction "C_C") (pintype "passive"))
      (node (ref "IC2.") (pin "3") (pinfunction "+IN_3") (pintype "input"))
      (node (ref "R8.") (pin "2") (pinfunction "2_2") (pintype "passive"))
    )
    (net (code "46") (name "Net-(IC2.A--IN)") (class "Default")
      (node (ref "IC2.") (pin "2") (pinfunction "-IN_2") (pintype "input"))
      (node (ref "R10.") (pin "2") (pinfunction "2_2") (pintype "passive"))
      (node (ref "R11.") (pin "1") (pinfunction "1_1") (pintype "passive"))
    )
    (net (code "47") (name "Net-(IC2.A-OUT)") (class "Default")
      (node (ref "IC2.") (pin "1") (pinfunction "OUT_1") (pintype "output"))
      (node (ref "R11.") (pin "2") (pinfunction "2_2") (pintype "passive"))
      (node (ref "R12.") (pin "1") (pinfunction "1_1") (pintype "passive"))
    )
    (net (code "48") (name "Net-(IC2.B--IN)") (class "Default")
      (node (ref "IC2.") (pin "6") (pinfunction "-IN_6") (pintype "input"))
      (node (ref "R7.") (pin "2") (pinfunction "2_2") (pintype "passive"))
      (node (ref "R8.") (pin "1") (pinfunction "1_1") (pintype "passive"))
      (node (ref "R9.") (pin "1") (pinfunction "1_1") (pintype "passive"))
    )
    (net (code "49") (name "Net-(IC2.B-OUT)") (class "Default")
      (node (ref "D1.") (pin "A") (pinfunction "A_A") (pintype "passive"))
      (node (ref "D2.") (pin "C") (pinfunction "C_C") (pintype "passive"))
      (node (ref "IC2.") (pin "7") (pinfunction "OUT_7") (pintype "output"))
    )
    (net (code "50") (name "Net-(IC2A-+IN)") (class "Default")
      (node (ref "D1") (pin "C") (pinfunction "C_C") (pintype "passive"))
      (node (ref "IC2") (pin "3") (pinfunction "+IN_3") (pintype "input"))
      (node (ref "R8") (pin "2") (pinfunction "2_2") (pintype "passive"))
    )
    (net (code "51") (name "Net-(IC2A--IN)") (class "Default")
      (node (ref "IC2") (pin "2") (pinfunction "-IN_2") (pintype "input"))
      (node (ref "R10") (pin "2") (pinfunction "2_2") (pintype "passive"))
      (node (ref "R11") (pin "1") (pinfunction "1_1") (pintype "passive"))
    )
    (net (code "52") (name "Net-(IC2A-OUT)") (class "Default")
      (node (ref "IC2") (pin "1") (pinfunction "OUT_1") (pintype "output"))
      (node (ref "R11") (pin "2") (pinfunction "2_2") (pintype "passive"))
      (node (ref "R12") (pin "1") (pinfunction "1_1") (pintype "passive"))
    )
    (net (code "53") (name "Net-(IC2B--IN)") (class "Default")
      (node (ref "IC2") (pin "6") (pinfunction "-IN_6") (pintype "input"))
      (node (ref "R7") (pin "2") (pinfunction "2_2") (pintype "passive"))
      (node (ref "R8") (pin "1") (pinfunction "1_1") (pintype "passive"))
      (node (ref "R9") (pin "1") (pinfunction "1_1") (pintype "passive"))
    )
    (net (code "54") (name "Net-(IC2B-OUT)") (class "Default")
      (node (ref "D1") (pin "A") (pinfunction "A_A") (pintype "passive"))
      (node (ref "D2") (pin "C") (pinfunction "C_C") (pintype "passive"))
      (node (ref "IC2") (pin "7") (pinfunction "OUT_7") (pintype "output"))
    )
    (net (code "55") (name "Net-(IC3-+IN)") (class "Default")
      (node (ref "C6") (pin "2") (pinfunction "2_2") (pintype "passive"))
      (node (ref "IC3") (pin "3") (pinfunction "+IN_3") (pintype "input"))
      (node (ref "R13") (pin "2") (pinfunction "2_2") (pintype "passive"))
    )
    (net (code "56") (name "Net-(IC3--IN)") (class "Default")
      (node (ref "C5") (pin "1") (pinfunction "1_1") (pintype "passive"))
      (node (ref "IC3") (pin "2") (pinfunction "-IN_2") (pintype "input"))
      (node (ref "IC3") (pin "6") (pinfunction "OUT_6") (pintype "output"))
      (node (ref "R14") (pin "1") (pinfunction "1_1") (pintype "passive"))
      (node (ref "R15") (pin "2") (pinfunction "2_2") (pintype "passive"))
    )
    (net (code "57") (name "Net-(IC3.-+IN)") (class "Default")
      (node (ref "C6.") (pin "2") (pinfunction "2_2") (pintype "passive"))
      (node (ref "IC3.") (pin "3") (pinfunction "+IN_3") (pintype "input"))
      (node (ref "R13.") (pin "2") (pinfunction "2_2") (pintype "passive"))
    )
    (net (code "58") (name "Net-(IC3.--IN)") (class "Default")
      (node (ref "C5.") (pin "1") (pinfunction "1_1") (pintype "passive"))
      (node (ref "IC3.") (pin "2") (pinfunction "-IN_2") (pintype "input"))
      (node (ref "IC3.") (pin "6") (pinfunction "OUT_6") (pintype "output"))
      (node (ref "R14.") (pin "1") (pinfunction "1_1") (pintype "passive"))
      (node (ref "R15.") (pin "2") (pinfunction "2_2") (pintype "passive"))
    )
    (net (code "59") (name "Net-(IC4-+IN)") (class "Default")
      (node (ref "C7") (pin "1") (pinfunction "1_1") (pintype "passive"))
      (node (ref "IC4") (pin "3") (pinfunction "+IN_3") (pintype "input"))
      (node (ref "Q1") (pin "S") (pinfunction "S_S") (pintype "passive"))
    )
    (net (code "60") (name "Net-(IC4--IN)") (class "Default")
      (node (ref "IC4") (pin "2") (pinfunction "-IN_2") (pintype "input"))
      (node (ref "IC4") (pin "6") (pinfunction "OUT_6") (pintype "output"))
      (node (ref "IC5") (pin "3") (pinfunction "+IN_3") (pintype "input"))
      (node (ref "R17") (pin "1") (pinfunction "1_1") (pintype "passive"))
    )
    (net (code "61") (name "Net-(IC4.-+IN)") (class "Default")
      (node (ref "C7.") (pin "1") (pinfunction "1_1") (pintype "passive"))
      (node (ref "IC4.") (pin "3") (pinfunction "+IN_3") (pintype "input"))
      (node (ref "Q1.") (pin "S") (pinfunction "S_S") (pintype "passive"))
    )
    (net (code "62") (name "Net-(IC4.--IN)") (class "Default")
      (node (ref "IC4.") (pin "2") (pinfunction "-IN_2") (pintype "input"))
      (node (ref "IC4.") (pin "6") (pinfunction "OUT_6") (pintype "output"))
      (node (ref "IC5") (pin "5") (pinfunction "+IN_5") (pintype "input"))
      (node (ref "R17.") (pin "1") (pinfunction "1_1") (pintype "passive"))
    )
    (net (code "63") (name "Net-(IC5A--IN)") (class "Default")
      (node (ref "D4") (pin "C") (pinfunction "C_C") (pintype "passive"))
      (node (ref "IC5") (pin "2") (pinfunction "-IN_2") (pintype "input"))
      (node (ref "R18") (pin "1") (pinfunction "1_1") (pintype "passive"))
    )
    (net (code "64") (name "Net-(IC5A-OUT)") (class "Default")
      (node (ref "D4") (pin "A") (pinfunction "A_A") (pintype "passive"))
      (node (ref "IC5") (pin "1") (pinfunction "OUT_1") (pintype "output"))
      (node (ref "PR2") (pin "E") (pinfunction "E_E") (pintype "passive"))
    )
    (net (code "65") (name "Net-(IC5B--IN)") (class "Default")
      (node (ref "D4.") (pin "C") (pinfunction "C_C") (pintype "passive"))
      (node (ref "IC5") (pin "6") (pinfunction "-IN_6") (pintype "input"))
      (node (ref "R18.") (pin "1") (pinfunction "1_1") (pintype "passive"))
    )
    (net (code "66") (name "Net-(IC5B-OUT)") (class "Default")
      (node (ref "D4.") (pin "A") (pinfunction "A_A") (pintype "passive"))
      (node (ref "IC5") (pin "7") (pinfunction "OUT_7") (pintype "output"))
      (node (ref "PR2.") (pin "E") (pinfunction "E_E") (pintype "passive"))
    )
    (net (code "67") (name "Net-(IC6A-+IN)") (class "Default")
      (node (ref "IC6") (pin "3") (pinfunction "+IN_3") (pintype "input"))
      (node (ref "R32") (pin "2") (pinfunction "2_2") (pintype "passive"))
    )
    (net (code "68") (name "Net-(IC6A--IN)") (class "Default")
      (node (ref "IC6") (pin "4") (pinfunction "-IN_4") (pintype "input"))
      (node (ref "R27") (pin "2") (pinfunction "2_2") (pintype "passive"))
      (node (ref "R31") (pin "1") (pinfunction "1_1") (pintype "passive"))
    )
    (net (code "69") (name "Net-(IC6A-AMP{slash}BIAS)") (class "Default")
      (node (ref "IC6") (pin "1") (pinfunction "AMP/BIAS_1") (pintype "passive"))
      (node (ref "R20") (pin "1") (pinfunction "1_1") (pintype "passive"))
    )
    (net (code "70") (name "Net-(IC6A-BUFF{slash}IN)") (class "Default")
      (node (ref "IC6") (pin "7") (pinfunction "BUFF/IN_7") (pintype "input"))
      (node (ref "RV1") (pin "1S") (pinfunction "1S_1S") (pintype "passive"))
    )
    (net (code "71") (name "Net-(IC6A-BUFF{slash}OUT)") (class "Default")
      (node (ref "C12") (pin "2") (pinfunction "2_2") (pintype "passive"))
      (node (ref "IC6") (pin "8") (pinfunction "BUFF/OUT_8") (pintype "output"))
      (node (ref "R29") (pin "1") (pinfunction "1_1") (pintype "passive"))
    )
    (net (code "72") (name "Net-(IC6A-DIODE{slash}BIAS)") (class "Default")
      (node (ref "IC6") (pin "2") (pinfunction "DIODE/BIAS_2") (pintype "passive"))
      (node (ref "R28") (pin "1") (pinfunction "1_1") (pintype "passive"))
    )
    (net (code "73") (name "Net-(IC6A-OUT)") (class "Default")
      (node (ref "IC6") (pin "5") (pinfunction "OUT_5") (pintype "output"))
      (node (ref "RV1") (pin "1E") (pinfunction "1E_1E") (pintype "passive"))
    )
    (net (code "74") (name "Net-(IC6B-+IN)") (class "Default")
      (node (ref "IC6") (pin "14") (pinfunction "+IN_14") (pintype "input"))
      (node (ref "R32.") (pin "2") (pinfunction "2_2") (pintype "passive"))
    )
    (net (code "75") (name "Net-(IC6B--IN)") (class "Default")
      (node (ref "IC6") (pin "13") (pinfunction "-IN_13") (pintype "input"))
      (node (ref "R27.") (pin "2") (pinfunction "2_2") (pintype "passive"))
      (node (ref "R31.") (pin "1") (pinfunction "1_1") (pintype "passive"))
    )
    (net (code "76") (name "Net-(IC6B-AMP{slash}BIAS)") (class "Default")
      (node (ref "IC6") (pin "16") (pinfunction "AMP/BIAS_16") (pintype "passive"))
      (node (ref "R20.") (pin "1") (pinfunction "1_1") (pintype "passive"))
    )
    (net (code "77") (name "Net-(IC6B-BUFF{slash}IN)") (class "Default")
      (node (ref "IC6") (pin "10") (pinfunction "BUFF/IN_10") (pintype "input"))
      (node (ref "RV1.") (pin "1S") (pinfunction "1S_1S") (pintype "passive"))
    )
    (net (code "78") (name "Net-(IC6B-BUFF{slash}OUT)") (class "Default")
      (node (ref "C12.") (pin "2") (pinfunction "2_2") (pintype "passive"))
      (node (ref "IC6") (pin "9") (pinfunction "BUFF/OUT_9") (pintype "output"))
      (node (ref "R29.") (pin "1") (pinfunction "1_1") (pintype "passive"))
    )
    (net (code "79") (name "Net-(IC6B-DIODE{slash}BIAS)") (class "Default")
      (node (ref "IC6") (pin "15") (pinfunction "DIODE/BIAS_15") (pintype "passive"))
      (node (ref "R28.") (pin "1") (pinfunction "1_1") (pintype "passive"))
    )
    (net (code "80") (name "Net-(IC6B-OUT)") (class "Default")
      (node (ref "IC6") (pin "12") (pinfunction "OUT_12") (pintype "output"))
      (node (ref "RV1.") (pin "1E") (pinfunction "1E_1E") (pintype "passive"))
    )
    (net (code "81") (name "Net-(IC7.A-+IN)") (class "Default")
      (node (ref "IC7.") (pin "3") (pinfunction "+IN_3") (pintype "input"))
      (node (ref "P11.") (pin "2") (pinfunction "2_2") (pintype "passive"))
      (node (ref "P12.") (pin "2") (pinfunction "2_2") (pintype "passive"))
    )
    (net (code "82") (name "Net-(IC7.A--IN)") (class "Default")
      (node (ref "IC7.") (pin "2") (pinfunction "-IN_2") (pintype "input"))
      (node (ref "P10.") (pin "2") (pinfunction "2_2") (pintype "passive"))
      (node (ref "P10.") (pin "3") (pinfunction "2_3") (pintype "passive"))
      (node (ref "RE7.") (pin "2") (pinfunction "2_2") (pintype "passive"))
      (node (ref "RE8.") (pin "1") (pinfunction "1_1") (pintype "passive"))
    )
    (net (code "83") (name "Net-(IC7.A-OUT)") (class "Default")
      (node (ref "CE5.") (pin "1") (pinfunction "1_1") (pintype "passive"))
      (node (ref "IC7.") (pin "1") (pinfunction "OUT_1") (pintype "output"))
      (node (ref "P13.") (pin "2") (pinfunction "2_2") (pintype "passive"))
      (node (ref "P13.") (pin "3") (pinfunction "2_3") (pintype "passive"))
      (node (ref "RE8.") (pin "2") (pinfunction "2_2") (pintype "passive"))
    )
    (net (code "84") (name "Net-(IC7.B-+IN)") (class "Default")
      (node (ref "IC7.") (pin "5") (pinfunction "+IN_5") (pintype "input"))
      (node (ref "P15.") (pin "2") (pinfunction "2_2") (pintype "passive"))
      (node (ref "P16.") (pin "2") (pinfunction "2_2") (pintype "passive"))
    )
    (net (code "85") (name "Net-(IC7.B--IN)") (class "Default")
      (node (ref "IC7.") (pin "6") (pinfunction "-IN_6") (pintype "input"))
      (node (ref "P14.") (pin "1") (pinfunction "1_1") (pintype "passive"))
      (node (ref "RE10.") (pin "1") (pinfunction "1_1") (pintype "passive"))
    )
    (net (code "86") (name "Net-(IC7.B-OUT)") (class "Default")
      (node (ref "CE6.") (pin "1") (pinfunction "1_1") (pintype "passive"))
      (node (ref "IC7.") (pin "7") (pinfunction "OUT_7") (pintype "output"))
      (node (ref "R27.") (pin "1") (pinfunction "1_1") (pintype "passive"))
      (node (ref "RE10.") (pin "2") (pinfunction "2_2") (pintype "passive"))
    )
    (net (code "87") (name "Net-(IC7A-+IN)") (class "Default")
      (node (ref "IC7") (pin "3") (pinfunction "+IN_3") (pintype "input"))
      (node (ref "P11") (pin "2") (pinfunction "2_2") (pintype "passive"))
      (node (ref "P12") (pin "2") (pinfunction "2_2") (pintype "passive"))
      (node (ref "RE6") (pin "2") (pinfunction "2_2") (pintype "passive"))
    )
    (net (code "88") (name "Net-(IC7A--IN)") (class "Default")
      (node (ref "IC7") (pin "2") (pinfunction "-IN_2") (pintype "input"))
      (node (ref "P10") (pin "1") (pinfunction "1_1") (pintype "passive"))
      (node (ref "RE7") (pin "2") (pinfunction "2_2") (pintype "passive"))
      (node (ref "RE8") (pin "1") (pinfunction "1_1") (pintype "passive"))
    )
    (net (code "89") (name "Net-(IC7A-OUT)") (class "Default")
      (node (ref "CE5") (pin "1") (pinfunction "1_1") (pintype "passive"))
      (node (ref "IC7") (pin "1") (pinfunction "OUT_1") (pintype "output"))
      (node (ref "P13") (pin "1") (pinfunction "1_1") (pintype "passive"))
      (node (ref "RE8") (pin "2") (pinfunction "2_2") (pintype "passive"))
    )
    (net (code "90") (name "Net-(IC7B-+IN)") (class "Default")
      (node (ref "IC7") (pin "5") (pinfunction "+IN_5") (pintype "input"))
      (node (ref "P15") (pin "2") (pinfunction "2_2") (pintype "passive"))
      (node (ref "P16") (pin "2") (pinfunction "2_2") (pintype "passive"))
      (node (ref "P16") (pin "3") (pinfunction "2_3") (pintype "passive"))
    )
    (net (code "91") (name "Net-(IC7B--IN)") (class "Default")
      (node (ref "IC7") (pin "6") (pinfunction "-IN_6") (pintype "input"))
      (node (ref "P14") (pin "1") (pinfunction "1_1") (pintype "passive"))
      (node (ref "RE10") (pin "1") (pinfunction "1_1") (pintype "passive"))
    )
    (net (code "92") (name "Net-(IC7B-OUT)") (class "Default")
      (node (ref "CE6") (pin "1") (pinfunction "1_1") (pintype "passive"))
      (node (ref "IC7") (pin "7") (pinfunction "OUT_7") (pintype "output"))
      (node (ref "R27") (pin "1") (pinfunction "1_1") (pintype "passive"))
      (node (ref "RE10") (pin "2") (pinfunction "2_2") (pintype "passive"))
    )
    (net (code "93") (name "Net-(P15.-Pad1)") (class "Default")
      (node (ref "P15.") (pin "1") (pinfunction "1_1") (pintype "passive"))
      (node (ref "RE9.") (pin "2") (pinfunction "2_2") (pintype "passive"))
    )
    (net (code "94") (name "Net-(PR2-PadA)") (class "Default")
      (node (ref "PR2") (pin "A") (pinfunction "A_A") (pintype "passive"))
      (node (ref "PR2") (pin "S") (pinfunction "S_S") (pintype "passive"))
      (node (ref "PR2") (pin "S0") (pinfunction "S_S0") (pintype "passive"))
      (node (ref "Q2") (pin "E") (pinfunction "E_E") (pintype "passive"))
      (node (ref "R19") (pin "1") (pinfunction "1_1") (pintype "passive"))
    )
    (net (code "95") (name "Net-(PR2.-PadA)") (class "Default")
      (node (ref "PR2.") (pin "A") (pinfunction "A_A") (pintype "passive"))
      (node (ref "PR2.") (pin "S") (pinfunction "S_S") (pintype "passive"))
      (node (ref "PR2.") (pin "S0") (pinfunction "S_S0") (pintype "passive"))
      (node (ref "Q2.") (pin "E") (pinfunction "E_E") (pintype "passive"))
      (node (ref "R19.") (pin "1") (pinfunction "1_1") (pintype "passive"))
    )
    (net (code "96") (name "Net-(PR3-PadS)") (class "Default")
      (node (ref "PR3") (pin "S") (pinfunction "S_S") (pintype "passive"))
      (node (ref "PR3") (pin "S0") (pinfunction "S_S0") (pintype "passive"))
      (node (ref "R19") (pin "2") (pinfunction "2_2") (pintype "passive"))
    )
    (net (code "97") (name "Net-(PR3.-PadS)") (class "Default")
      (node (ref "PR3.") (pin "S") (pinfunction "S_S") (pintype "passive"))
      (node (ref "PR3.") (pin "S0") (pinfunction "S_S0") (pintype "passive"))
      (node (ref "R19.") (pin "2") (pinfunction "2_2") (pintype "passive"))
    )
    (net (code "98") (name "Net-(PR4-PadA)") (class "Default")
      (node (ref "PR4") (pin "A") (pinfunction "A_A") (pintype "passive"))
      (node (ref "R31") (pin "2") (pinfunction "2_2") (pintype "passive"))
    )
    (net (code "99") (name "Net-(PR4-PadE)") (class "Default")
      (node (ref "PR4") (pin "E") (pinfunction "E_E") (pintype "passive"))
      (node (ref "R32") (pin "1") (pinfunction "1_1") (pintype "passive"))
    )
    (net (code "100") (name "Net-(PR4.-PadA)") (class "Default")
      (node (ref "PR4.") (pin "A") (pinfunction "A_A") (pintype "passive"))
      (node (ref "R31.") (pin "2") (pinfunction "2_2") (pintype "passive"))
    )
    (net (code "101") (name "Net-(PR4.-PadE)") (class "Default")
      (node (ref "PR4.") (pin "E") (pinfunction "E_E") (pintype "passive"))
      (node (ref "R32.") (pin "1") (pinfunction "1_1") (pintype "passive"))
    )
    (net (code "102") (name "Net-(Q1-D-PadD2)") (class "Default")
      (node (ref "Q1") (pin "D") (pinfunction "D_D") (pintype "passive"))
      (node (ref "Q1") (pin "D2") (pinfunction "D_D2") (pintype "passive"))
      (node (ref "R15") (pin "1") (pinfunction "1_1") (pintype "passive"))
      (node (ref "R16") (pin "2") (pinfunction "2_2") (pintype "passive"))
    )
    (net (code "103") (name "Net-(Q1.-D-PadD2)") (class "Default")
      (node (ref "Q1.") (pin "D") (pinfunction "D_D") (pintype "passive"))
      (node (ref "Q1.") (pin "D2") (pinfunction "D_D2") (pintype "passive"))
      (node (ref "R15.") (pin "1") (pinfunction "1_1") (pintype "passive"))
      (node (ref "R16.") (pin "2") (pinfunction "2_2") (pintype "passive"))
    )
    (net (code "104") (name "Net-(Q2-PadC)") (class "Default")
      (node (ref "Q2") (pin "C") (pinfunction "C_C") (pintype "passive"))
      (node (ref "R20") (pin "2") (pinfunction "2_2") (pintype "passive"))
    )
    (net (code "105") (name "Net-(Q2.-PadC)") (class "Default")
      (node (ref "Q2.") (pin "C") (pinfunction "C_C") (pintype "passive"))
      (node (ref "R20.") (pin "2") (pinfunction "2_2") (pintype "passive"))
    )
    (net (code "106") (name "unconnected-(IC3-ON1-Pad1)") (class "Default")
      (node (ref "IC3") (pin "1") (pinfunction "ON1_1") (pintype "passive"))
    )
    (net (code "107") (name "unconnected-(IC3-ON2-Pad5)") (class "Default")
      (node (ref "IC3") (pin "5") (pinfunction "ON2_5") (pintype "passive"))
    )
    (net (code "108") (name "unconnected-(IC3-OPT-Pad8)") (class "Default")
      (node (ref "IC3") (pin "8") (pinfunction "OPT_8") (pintype "passive"))
    )
    (net (code "109") (name "unconnected-(IC3.-ON1-Pad1)") (class "Default")
      (node (ref "IC3.") (pin "1") (pinfunction "ON1_1") (pintype "passive"))
    )
    (net (code "110") (name "unconnected-(IC3.-ON2-Pad5)") (class "Default")
      (node (ref "IC3.") (pin "5") (pinfunction "ON2_5") (pintype "passive"))
    )
    (net (code "111") (name "unconnected-(IC3.-OPT-Pad8)") (class "Default")
      (node (ref "IC3.") (pin "8") (pinfunction "OPT_8") (pintype "passive"))
    )
    (net (code "112") (name "unconnected-(IC4-ON1-Pad1)") (class "Default")
      (node (ref "IC4") (pin "1") (pinfunction "ON1_1") (pintype "passive"))
    )
    (net (code "113") (name "unconnected-(IC4-ON2-Pad5)") (class "Default")
      (node (ref "IC4") (pin "5") (pinfunction "ON2_5") (pintype "passive"))
    )
    (net (code "114") (name "unconnected-(IC4-OPT-Pad8)") (class "Default")
      (node (ref "IC4") (pin "8") (pinfunction "OPT_8") (pintype "passive"))
    )
    (net (code "115") (name "unconnected-(IC4.-ON1-Pad1)") (class "Default")
      (node (ref "IC4.") (pin "1") (pinfunction "ON1_1") (pintype "passive"))
    )
    (net (code "116") (name "unconnected-(IC4.-ON2-Pad5)") (class "Default")
      (node (ref "IC4.") (pin "5") (pinfunction "ON2_5") (pintype "passive"))
    )
    (net (code "117") (name "unconnected-(IC4.-OPT-Pad8)") (class "Default")
      (node (ref "IC4.") (pin "8") (pinfunction "OPT_8") (pintype "passive"))
    )
  )
)
